# EasyEDA_Schematic_Split_Flap_Remote_Boar.net
KiCad netlist of a schematic drawn in EasyEDA
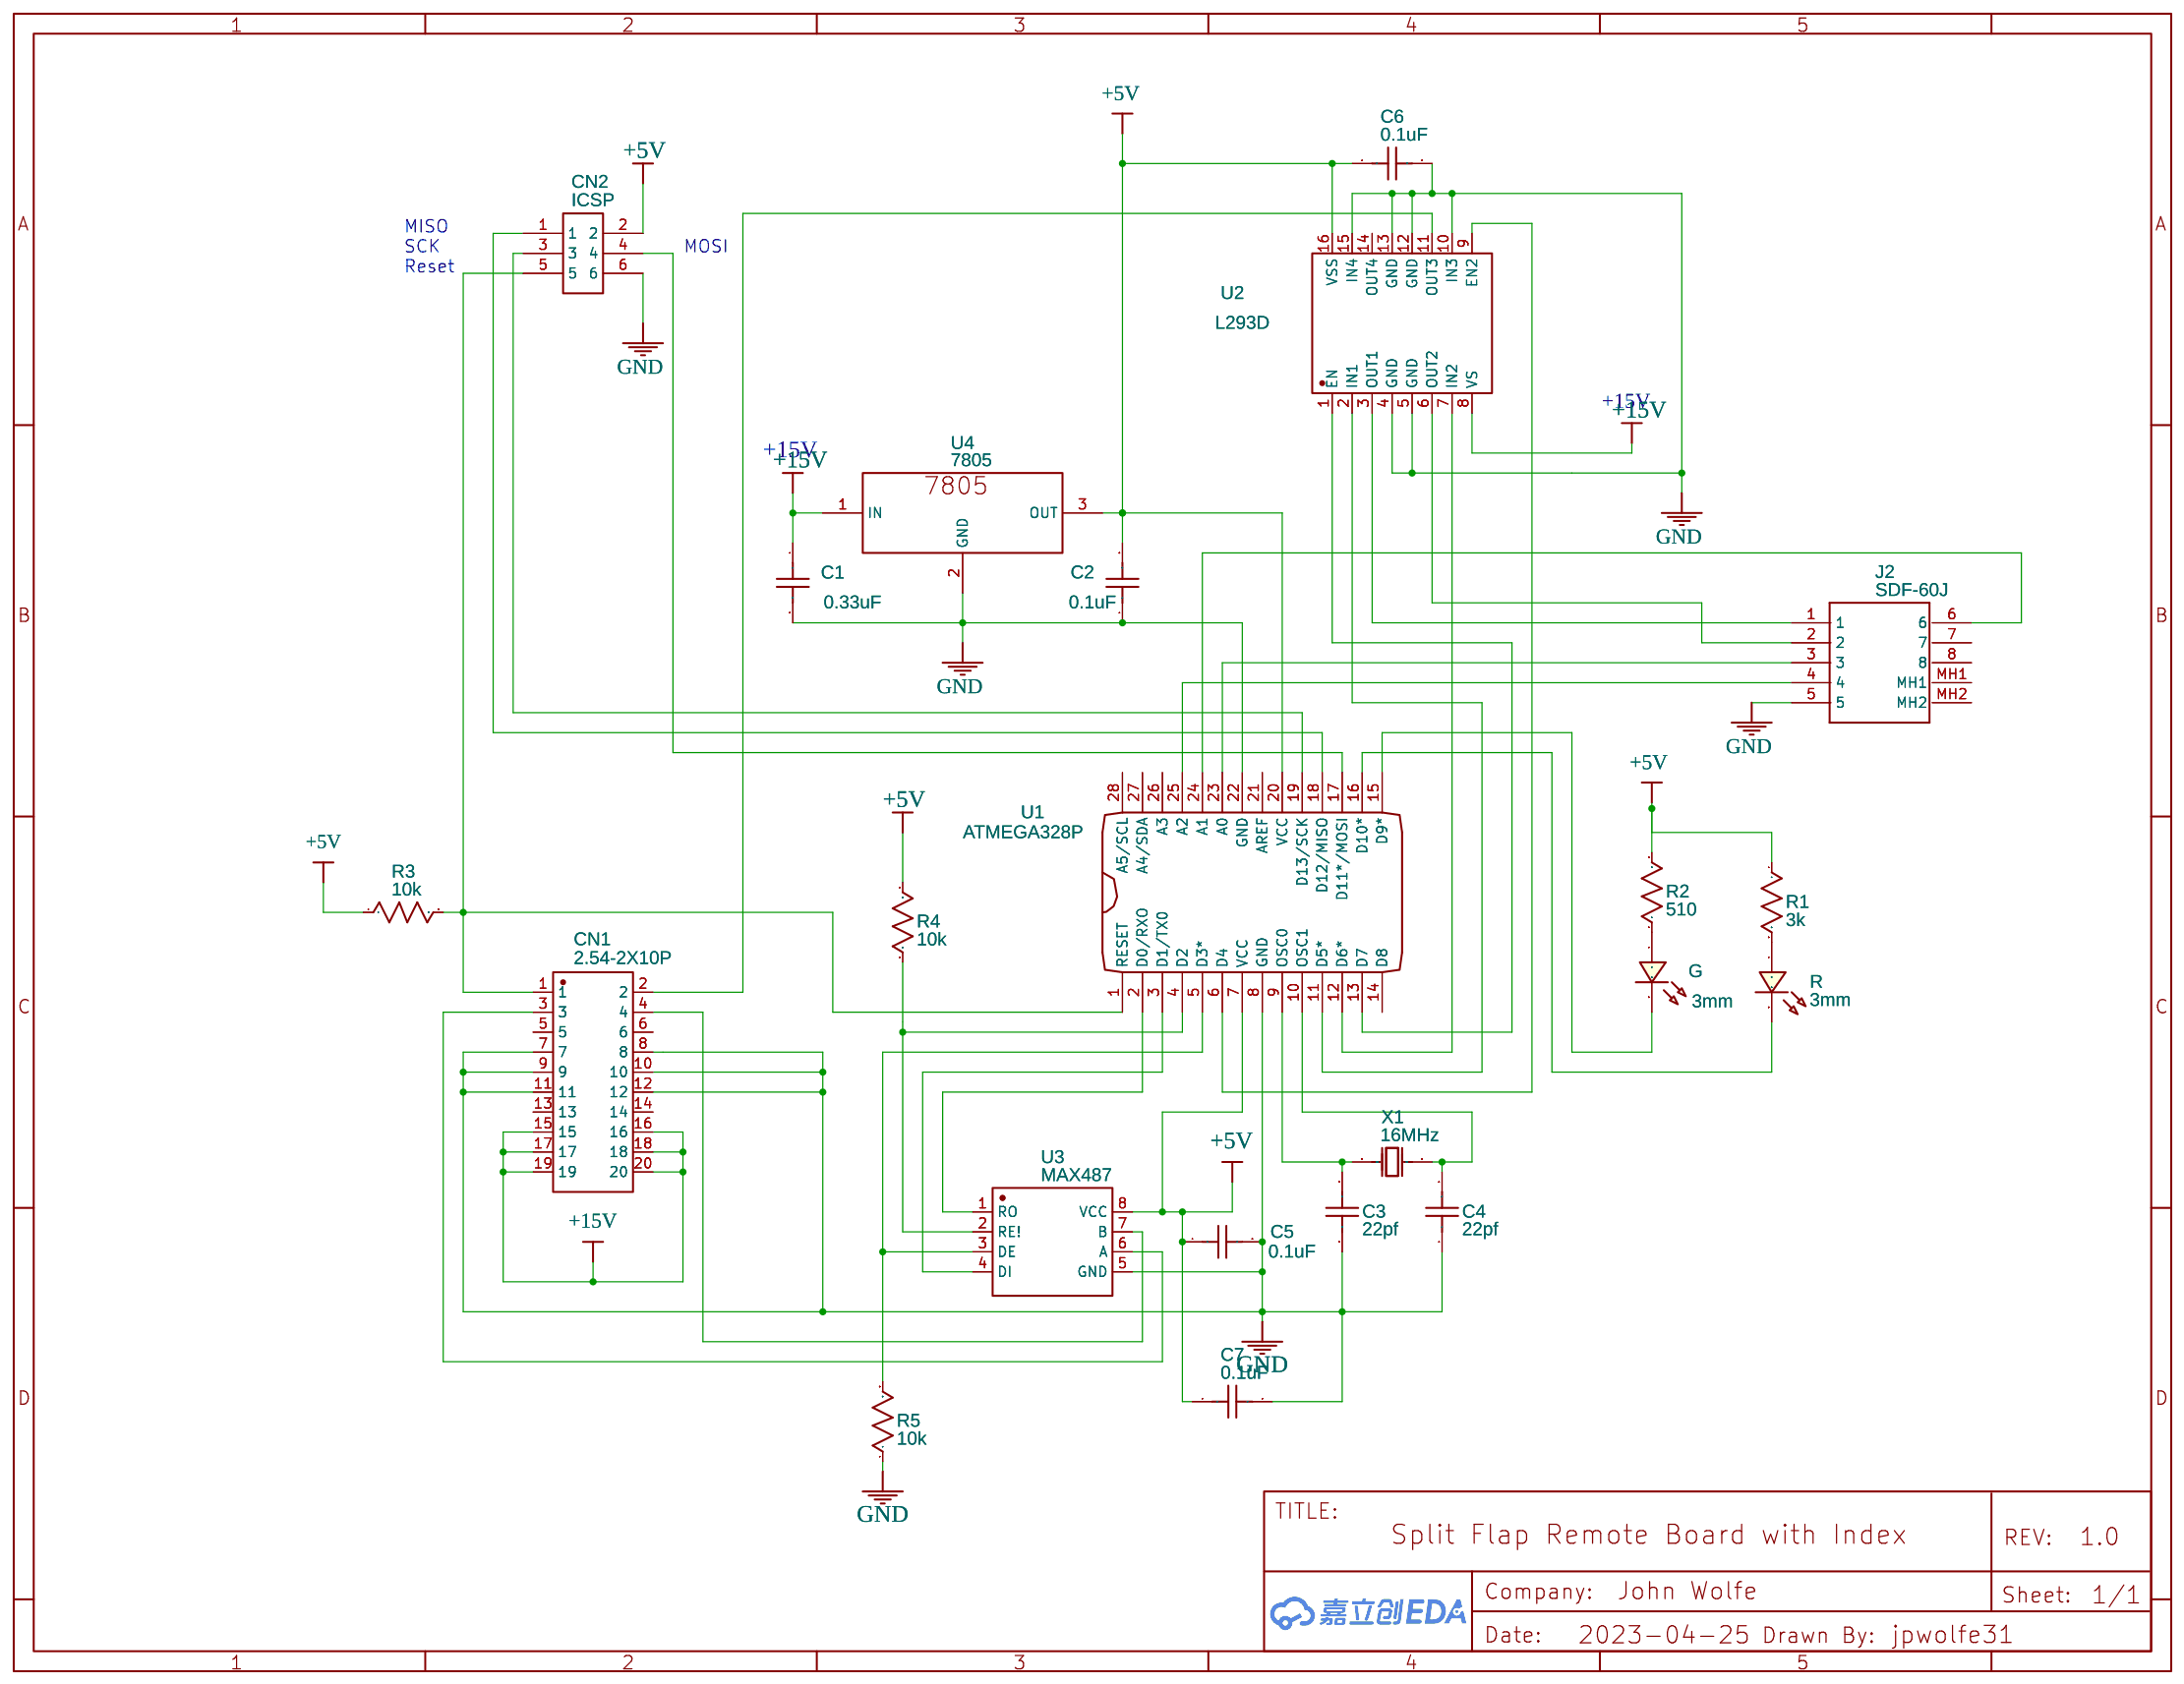
[diagram p0: schematic sheet]

(export (version "E")
  (design (tool "Eeschema 10.0.6"))
  (components
    (comp (ref "C1") (value "0.33uF") (libsource (lib "") (part "C_RAD-0.2_US")))
    (comp (ref "C2") (value "0.1uF") (libsource (lib "") (part "C_RAD-0.1_US")))
    (comp (ref "C3") (value "22pf") (libsource (lib "") (part "C_RAD-0.1_US")))
    (comp (ref "C4") (value "22pf") (libsource (lib "") (part "C_RAD-0.1_US")))
    (comp (ref "C5") (value "0.1uF") (libsource (lib "") (part "C_RAD-0.1_US_1")))
    (comp (ref "C6") (value "0.1uF") (libsource (lib "") (part "C_RAD-0.1_US_1")))
    (comp (ref "C7") (value "0.1uF") (libsource (lib "") (part "C_RAD-0.1_US_1")))
    (comp (ref "CN1")
      (value "2.54-2X10P")
      (fields
        (field (name "Manufacturer Part") "KH-DC3-2.54-2X10P")
        (field (name "Manufacturer") "kinghelm(金航标)")
      )
      (libsource (lib "") (part "KH-DC3-2.54-2X10P"))
    )
    (comp (ref "CN2") (value "ICSP") (libsource (lib "") (part "ICSP")))
    (comp (ref "G")
      (value "3mm")
      (fields
        (field (name "Manufacturer Part") "204-10SYGD/S530-E3")
        (field (name "Manufacturer") "EVERLIGHT(台湾亿光)")
      )
      (libsource (lib "") (part "LED-TH-3mm_G"))
    )
    (comp (ref "J2") (value "SDF-60J") (libsource (lib "") (part "SDF-60J")))
    (comp (ref "R")
      (value "3mm")
      (fields
        (field (name "Manufacturer Part") "204-10SDRD/S530-A3-L")
        (field (name "Manufacturer") "EVERLIGHT(台湾亿光)")
      )
      (libsource (lib "") (part "LED-TH-3mm_R"))
    )
    (comp (ref "R1") (value "3k") (libsource (lib "") (part "R_AXIAL-0.3_US_2")))
    (comp (ref "R2") (value "510") (libsource (lib "") (part "R_AXIAL-0.3_US")))
    (comp (ref "R3") (value "10k") (libsource (lib "") (part "R_AXIAL-0.3_US_1")))
    (comp (ref "R4") (value "10k") (libsource (lib "") (part "R_AXIAL-0.3_US")))
    (comp (ref "R5") (value "10k") (libsource (lib "") (part "R_AXIAL-0.3_US")))
    (comp (ref "U1") (value "ATMEGA328P") (libsource (lib "") (part "ATMEGA328 NEW")))
    (comp (ref "U2")
      (value "L293D")
      (fields (field (name "Manufacturer") "Gcore"))
      (libsource (lib "") (part "L293D_C504385"))
    )
    (comp (ref "U3")
      (value "MAX487")
      (fields
        (field (name "Manufacturer Part") "MAX487CPA+")
        (field (name "Manufacturer") "ADI(亚德诺)/MAXIM(美信)")
      )
      (libsource (lib "") (part "MAX487CPA+"))
    )
    (comp (ref "U4") (value "7805") (libsource (lib "") (part "7805")))
    (comp (ref "X1")
      (value "16MHz")
      (fields (field (name "Manufacturer Part") "X49SD16MSD2SC") (field (name "Manufacturer") "YXC"))
      (libsource (lib "") (part "XTAL16MHZ DIP"))
    )
  )
  (nets
    (net (code "1") (name "+5V") (class "Default")
      (node (ref "C2") (pin "2") (pinfunction "2_2") (pintype "unspecified"))
      (node (ref "C5") (pin "1") (pinfunction "1_1") (pintype "unspecified"))
      (node (ref "C6") (pin "1") (pinfunction "1_1") (pintype "unspecified"))
      (node (ref "C7") (pin "1") (pinfunction "1_1") (pintype "unspecified"))
      (node (ref "CN2") (pin "2") (pinfunction "2_2") (pintype "unspecified"))
      (node (ref "R1") (pin "1") (pinfunction "1_1") (pintype "unspecified"))
      (node (ref "R2") (pin "2") (pinfunction "2_2") (pintype "unspecified"))
      (node (ref "R3") (pin "1") (pinfunction "1_1") (pintype "unspecified"))
      (node (ref "R4") (pin "2") (pinfunction "2_2") (pintype "unspecified"))
      (node (ref "U1") (pin "20") (pinfunction "VCC_20") (pintype "unspecified"))
      (node (ref "U1") (pin "7") (pinfunction "VCC_7") (pintype "unspecified"))
      (node (ref "U2") (pin "16") (pinfunction "VSS_16") (pintype "unspecified"))
      (node (ref "U3") (pin "8") (pinfunction "VCC_8") (pintype "unspecified"))
      (node (ref "U4") (pin "3") (pinfunction "OUT_3") (pintype "unspecified"))
    )
    (net (code "2") (name "+15V") (class "Default")
      (node (ref "C1") (pin "1") (pinfunction "1_1") (pintype "unspecified"))
      (node (ref "CN1") (pin "15") (pinfunction "15_15") (pintype "unspecified"))
      (node (ref "CN1") (pin "16") (pinfunction "16_16") (pintype "unspecified"))
      (node (ref "CN1") (pin "17") (pinfunction "17_17") (pintype "unspecified"))
      (node (ref "CN1") (pin "18") (pinfunction "18_18") (pintype "unspecified"))
      (node (ref "CN1") (pin "19") (pinfunction "19_19") (pintype "unspecified"))
      (node (ref "CN1") (pin "20") (pinfunction "20_20") (pintype "unspecified"))
      (node (ref "U2") (pin "8") (pinfunction "VS_8") (pintype "unspecified"))
      (node (ref "U4") (pin "1") (pinfunction "IN_1") (pintype "unspecified"))
    )
    (net (code "3") (name "GND") (class "Default")
      (node (ref "C1") (pin "2") (pinfunction "2_2") (pintype "unspecified"))
      (node (ref "C2") (pin "1") (pinfunction "1_1") (pintype "unspecified"))
      (node (ref "C3") (pin "1") (pinfunction "1_1") (pintype "unspecified"))
      (node (ref "C4") (pin "1") (pinfunction "1_1") (pintype "unspecified"))
      (node (ref "C5") (pin "2") (pinfunction "2_2") (pintype "unspecified"))
      (node (ref "C6") (pin "2") (pinfunction "2_2") (pintype "unspecified"))
      (node (ref "C7") (pin "2") (pinfunction "2_2") (pintype "unspecified"))
      (node (ref "CN1") (pin "10") (pinfunction "10_10") (pintype "unspecified"))
      (node (ref "CN1") (pin "11") (pinfunction "11_11") (pintype "unspecified"))
      (node (ref "CN1") (pin "12") (pinfunction "12_12") (pintype "unspecified"))
      (node (ref "CN1") (pin "7") (pinfunction "7_7") (pintype "unspecified"))
      (node (ref "CN1") (pin "8") (pinfunction "8_8") (pintype "unspecified"))
      (node (ref "CN1") (pin "9") (pinfunction "9_9") (pintype "unspecified"))
      (node (ref "CN2") (pin "6") (pinfunction "6_6") (pintype "unspecified"))
      (node (ref "J2") (pin "5") (pinfunction "5_5") (pintype "bidirectional"))
      (node (ref "R5") (pin "1") (pinfunction "1_1") (pintype "unspecified"))
      (node (ref "U1") (pin "22") (pinfunction "GND_22") (pintype "unspecified"))
      (node (ref "U1") (pin "8") (pinfunction "GND_8") (pintype "unspecified"))
      (node (ref "U2") (pin "10") (pinfunction "IN3_10") (pintype "unspecified"))
      (node (ref "U2") (pin "12") (pinfunction "GND_12") (pintype "unspecified"))
      (node (ref "U2") (pin "13") (pinfunction "GND_13") (pintype "unspecified"))
      (node (ref "U2") (pin "15") (pinfunction "IN4_15") (pintype "unspecified"))
      (node (ref "U2") (pin "4") (pinfunction "GND_4") (pintype "unspecified"))
      (node (ref "U2") (pin "5") (pinfunction "GND_5") (pintype "unspecified"))
      (node (ref "U3") (pin "5") (pinfunction "GND_5") (pintype "unspecified"))
      (node (ref "U4") (pin "2") (pinfunction "GND_2") (pintype "unspecified"))
    )
    (net (code "4") (name "Net-(G-Pad1)") (class "Default")
      (node (ref "G") (pin "1") (pinfunction "1_1") (pintype "unspecified"))
      (node (ref "R2") (pin "1") (pinfunction "1_1") (pintype "unspecified"))
    )
    (net (code "5") (name "Net-(R-Pad1)") (class "Default")
      (node (ref "R") (pin "1") (pinfunction "1_1") (pintype "unspecified"))
      (node (ref "R1") (pin "2") (pinfunction "2_2") (pintype "unspecified"))
    )
    (net (code "6") (name "Net-(U1-A0)") (class "Default")
      (node (ref "J2") (pin "3") (pinfunction "3_3") (pintype "bidirectional"))
      (node (ref "U1") (pin "23") (pinfunction "A0_23") (pintype "unspecified"))
    )
    (net (code "7") (name "Net-(U1-A1)") (class "Default")
      (node (ref "J2") (pin "6") (pinfunction "6_6") (pintype "bidirectional"))
      (node (ref "U1") (pin "24") (pinfunction "A1_24") (pintype "unspecified"))
    )
    (net (code "8") (name "Net-(U1-A2)") (class "Default")
      (node (ref "J2") (pin "4") (pinfunction "4_4") (pintype "bidirectional"))
      (node (ref "U1") (pin "25") (pinfunction "A2_25") (pintype "unspecified"))
    )
    (net (code "9") (name "Net-(U1-D0{slash}RXO)") (class "Default")
      (node (ref "U1") (pin "2") (pinfunction "D0/RXO_2") (pintype "unspecified"))
      (node (ref "U3") (pin "1") (pinfunction "RO_1") (pintype "unspecified"))
    )
    (net (code "10") (name "Net-(U1-D1{slash}TX0)") (class "Default")
      (node (ref "U1") (pin "3") (pinfunction "D1/TX0_3") (pintype "unspecified"))
      (node (ref "U3") (pin "4") (pinfunction "DI_4") (pintype "unspecified"))
    )
    (net (code "11") (name "Net-(U1-D2)") (class "Default")
      (node (ref "R4") (pin "1") (pinfunction "1_1") (pintype "unspecified"))
      (node (ref "U1") (pin "4") (pinfunction "D2_4") (pintype "unspecified"))
      (node (ref "U3") (pin "2") (pinfunction "RE!_2") (pintype "unspecified"))
    )
    (net (code "12") (name "Net-(U1-D3*)") (class "Default")
      (node (ref "R5") (pin "2") (pinfunction "2_2") (pintype "unspecified"))
      (node (ref "U1") (pin "5") (pinfunction "D3*_5") (pintype "unspecified"))
      (node (ref "U3") (pin "3") (pinfunction "DE_3") (pintype "unspecified"))
    )
    (net (code "13") (name "Net-(U1-D4)") (class "Default")
      (node (ref "U1") (pin "6") (pinfunction "D4_6") (pintype "unspecified"))
      (node (ref "U2") (pin "9") (pinfunction "EN2_9") (pintype "unspecified"))
    )
    (net (code "14") (name "Net-(U1-D5*)") (class "Default")
      (node (ref "U1") (pin "11") (pinfunction "D5*_11") (pintype "unspecified"))
      (node (ref "U2") (pin "2") (pinfunction "IN1_2") (pintype "unspecified"))
    )
    (net (code "15") (name "Net-(U1-D6*)") (class "Default")
      (node (ref "U1") (pin "12") (pinfunction "D6*_12") (pintype "unspecified"))
      (node (ref "U2") (pin "7") (pinfunction "IN2_7") (pintype "unspecified"))
    )
    (net (code "16") (name "Net-(U1-D7)") (class "Default")
      (node (ref "U1") (pin "13") (pinfunction "D7_13") (pintype "unspecified"))
      (node (ref "U2") (pin "1") (pinfunction "EN_1") (pintype "unspecified"))
    )
    (net (code "17") (name "Net-(U1-D9*)") (class "Default")
      (node (ref "G") (pin "2") (pinfunction "2_2") (pintype "unspecified"))
      (node (ref "U1") (pin "15") (pinfunction "D9*_15") (pintype "unspecified"))
    )
    (net (code "18") (name "Net-(U1-D10*)") (class "Default")
      (node (ref "R") (pin "2") (pinfunction "2_2") (pintype "unspecified"))
      (node (ref "U1") (pin "16") (pinfunction "D10*_16") (pintype "unspecified"))
    )
    (net (code "19") (name "Net-(U1-D11*{slash}MOSI)") (class "Default")
      (node (ref "CN2") (pin "4") (pinfunction "4_4") (pintype "unspecified"))
      (node (ref "U1") (pin "17") (pinfunction "D11*/MOSI_17") (pintype "unspecified"))
    )
    (net (code "20") (name "Net-(U1-D12{slash}MISO)") (class "Default")
      (node (ref "CN2") (pin "1") (pinfunction "1_1") (pintype "unspecified"))
      (node (ref "U1") (pin "18") (pinfunction "D12/MISO_18") (pintype "unspecified"))
    )
    (net (code "21") (name "Net-(U1-D13{slash}SCK)") (class "Default")
      (node (ref "CN2") (pin "3") (pinfunction "3_3") (pintype "unspecified"))
      (node (ref "U1") (pin "19") (pinfunction "D13/SCK_19") (pintype "unspecified"))
    )
    (net (code "22") (name "Net-(U1-OSC0)") (class "Default")
      (node (ref "C3") (pin "2") (pinfunction "2_2") (pintype "unspecified"))
      (node (ref "U1") (pin "9") (pinfunction "OSC0_9") (pintype "unspecified"))
      (node (ref "X1") (pin "2") (pinfunction "OSC2_2") (pintype "input"))
    )
    (net (code "23") (name "Net-(U1-OSC1)") (class "Default")
      (node (ref "C4") (pin "2") (pinfunction "2_2") (pintype "unspecified"))
      (node (ref "U1") (pin "10") (pinfunction "OSC1_10") (pintype "unspecified"))
      (node (ref "X1") (pin "1") (pinfunction "OSC1_1") (pintype "input"))
    )
    (net (code "24") (name "Net-(U1-RESET)") (class "Default")
      (node (ref "CN1") (pin "1") (pinfunction "1_1") (pintype "unspecified"))
      (node (ref "CN2") (pin "5") (pinfunction "5_5") (pintype "unspecified"))
      (node (ref "R3") (pin "2") (pinfunction "2_2") (pintype "unspecified"))
      (node (ref "U1") (pin "1") (pinfunction "RESET_1") (pintype "unspecified"))
    )
    (net (code "25") (name "Net-(U2-OUT1)") (class "Default")
      (node (ref "J2") (pin "1") (pinfunction "1_1") (pintype "bidirectional"))
      (node (ref "U2") (pin "3") (pinfunction "OUT1_3") (pintype "unspecified"))
    )
    (net (code "26") (name "Net-(U2-OUT2)") (class "Default")
      (node (ref "J2") (pin "2") (pinfunction "2_2") (pintype "bidirectional"))
      (node (ref "U2") (pin "6") (pinfunction "OUT2_6") (pintype "unspecified"))
    )
    (net (code "27") (name "Net-(U2-OUT3)") (class "Default")
      (node (ref "CN1") (pin "2") (pinfunction "2_2") (pintype "unspecified"))
      (node (ref "U2") (pin "11") (pinfunction "OUT3_11") (pintype "unspecified"))
    )
    (net (code "28") (name "Net-(U3-A)") (class "Default")
      (node (ref "CN1") (pin "3") (pinfunction "3_3") (pintype "unspecified"))
      (node (ref "U3") (pin "6") (pinfunction "A_6") (pintype "unspecified"))
    )
    (net (code "29") (name "Net-(U3-B)") (class "Default")
      (node (ref "CN1") (pin "4") (pinfunction "4_4") (pintype "unspecified"))
      (node (ref "U3") (pin "7") (pinfunction "B_7") (pintype "unspecified"))
    )
    (net (code "30") (name "unconnected-(CN1-Pad5)") (class "Default")
      (node (ref "CN1") (pin "5") (pinfunction "5_5") (pintype "unspecified"))
    )
    (net (code "31") (name "unconnected-(CN1-Pad6)") (class "Default")
      (node (ref "CN1") (pin "6") (pinfunction "6_6") (pintype "unspecified"))
    )
    (net (code "32") (name "unconnected-(CN1-Pad13)") (class "Default")
      (node (ref "CN1") (pin "13") (pinfunction "13_13") (pintype "unspecified"))
    )
    (net (code "33") (name "unconnected-(CN1-Pad14)") (class "Default")
      (node (ref "CN1") (pin "14") (pinfunction "14_14") (pintype "unspecified"))
    )
    (net (code "34") (name "unconnected-(J2-Pad7)") (class "Default")
      (node (ref "J2") (pin "7") (pinfunction "7_7") (pintype "bidirectional"))
    )
    (net (code "35") (name "unconnected-(J2-Pad8)") (class "Default")
      (node (ref "J2") (pin "8") (pinfunction "8_8") (pintype "bidirectional"))
    )
    (net (code "36") (name "unconnected-(J2-PadMH1)") (class "Default")
      (node (ref "J2") (pin "MH1") (pinfunction "MH1_MH1") (pintype "bidirectional"))
    )
    (net (code "37") (name "unconnected-(J2-PadMH2)") (class "Default")
      (node (ref "J2") (pin "MH2") (pinfunction "MH2_MH2") (pintype "bidirectional"))
    )
    (net (code "38") (name "unconnected-(U1-A3-Pad26)") (class "Default")
      (node (ref "U1") (pin "26") (pinfunction "A3_26") (pintype "unspecified"))
    )
    (net (code "39") (name "unconnected-(U1-A4{slash}SDA-Pad27)") (class "Default")
      (node (ref "U1") (pin "27") (pinfunction "A4/SDA_27") (pintype "unspecified"))
    )
    (net (code "40") (name "unconnected-(U1-A5{slash}SCL-Pad28)") (class "Default")
      (node (ref "U1") (pin "28") (pinfunction "A5/SCL_28") (pintype "unspecified"))
    )
    (net (code "41") (name "unconnected-(U1-AREF-Pad21)") (class "Default")
      (node (ref "U1") (pin "21") (pinfunction "AREF_21") (pintype "unspecified"))
    )
    (net (code "42") (name "unconnected-(U1-D8-Pad14)") (class "Default")
      (node (ref "U1") (pin "14") (pinfunction "D8_14") (pintype "unspecified"))
    )
    (net (code "43") (name "unconnected-(U2-OUT4-Pad14)") (class "Default")
      (node (ref "U2") (pin "14") (pinfunction "OUT4_14") (pintype "unspecified"))
    )
  )
)
